# RF2ComLong.net
KiCad netlist of a schematic drawn in EAGLE
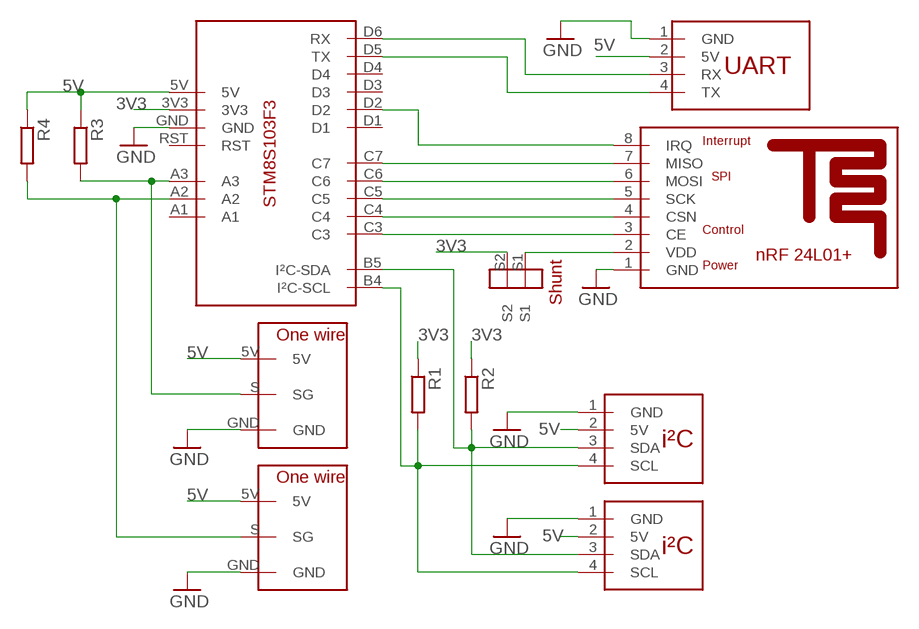
[diagram p0: schematic, sheet 1]

(export (version "E")
  (design (tool "Eeschema 10.0.6"))
  (components
    (comp (ref "R1")
      (value "1k")
      (footprint "eagle-import:R1206")
      (libsource (lib "eagle-import") (part "R-EU_R1206"))
    )
    (comp (ref "R2")
      (value "1k")
      (footprint "eagle-import:R1206")
      (libsource (lib "eagle-import") (part "R-EU_R1206"))
    )
    (comp (ref "R3")
      (value "1k")
      (footprint "eagle-import:R1206")
      (libsource (lib "eagle-import") (part "R-EU_R1206"))
    )
    (comp (ref "R4")
      (value "1k")
      (footprint "eagle-import:R1206")
      (libsource (lib "eagle-import") (part "R-EU_R1206"))
    )
    (comp (ref "U$1")
      (value "STM8S103F3-DEVKITMINI")
      (footprint "eagle-import:STM8S103F3-DEVKIT-MINI")
      (libsource (lib "eagle-import") (part "STM8S103F3-DEVKITMINI"))
    )
    (comp (ref "U$2")
      (value "NRF24L01+REFDESIGNMINI")
      (footprint "eagle-import:NRF24L01+REFDESIGN-MINI")
      (libsource (lib "eagle-import") (part "NRF24L01+REFDESIGNMINI"))
    )
    (comp (ref "U$3")
      (value "UARTMINI")
      (footprint "eagle-import:UART-MINI")
      (libsource (lib "eagle-import") (part "UARTMINI"))
    )
    (comp (ref "U$4")
      (value "I2CMINI")
      (footprint "eagle-import:I2C-MINI")
      (libsource (lib "eagle-import") (part "I2CMINI"))
    )
    (comp (ref "U$5")
      (value "ONE_WIRE")
      (footprint "eagle-import:ONE_WIRE")
      (libsource (lib "eagle-import") (part "ONE_WIRE"))
    )
    (comp (ref "U$6")
      (value "ONE_WIRE")
      (footprint "eagle-import:ONE_WIRE")
      (libsource (lib "eagle-import") (part "ONE_WIRE"))
    )
    (comp (ref "U$7")
      (value "I2CMINI")
      (footprint "eagle-import:I2C-MINI")
      (libsource (lib "eagle-import") (part "I2CMINI"))
    )
    (comp (ref "U$8")
      (value "SMD_SHUNT")
      (footprint "eagle-import:SMD_SHUNT")
      (libsource (lib "eagle-import") (part "SMD_SHUNT"))
    )
  )
  (nets
    (net (code "1") (name "/3V3") (class "Default")
      (node (ref "R1") (pin "1") (pinfunction "1_1") (pintype "passive"))
      (node (ref "R2") (pin "1") (pinfunction "1_1") (pintype "passive"))
      (node (ref "U$1") (pin "3V3") (pinfunction "3V3_3V3") (pintype "bidirectional"))
      (node (ref "U$8") (pin "S2") (pinfunction "S2_S2") (pintype "bidirectional"))
    )
    (net (code "2") (name "/5V") (class "Default")
      (node (ref "R3") (pin "1") (pinfunction "1_1") (pintype "passive"))
      (node (ref "R4") (pin "1") (pinfunction "1_1") (pintype "passive"))
      (node (ref "U$1") (pin "5V") (pinfunction "5V_5V") (pintype "bidirectional"))
      (node (ref "U$3") (pin "2") (pinfunction "5V_2") (pintype "bidirectional"))
      (node (ref "U$4") (pin "2") (pinfunction "5V_2") (pintype "bidirectional"))
      (node (ref "U$5") (pin "5V") (pinfunction "5V_5V") (pintype "bidirectional"))
      (node (ref "U$6") (pin "5V") (pinfunction "5V_5V") (pintype "bidirectional"))
      (node (ref "U$7") (pin "2") (pinfunction "5V_2") (pintype "bidirectional"))
    )
    (net (code "3") (name "GND") (class "Default")
      (node (ref "U$1") (pin "GND") (pinfunction "GND_GND") (pintype "bidirectional"))
      (node (ref "U$2") (pin "1") (pinfunction "GND_1") (pintype "bidirectional"))
      (node (ref "U$3") (pin "1") (pinfunction "GND_1") (pintype "bidirectional"))
      (node (ref "U$4") (pin "1") (pinfunction "GND_1") (pintype "bidirectional"))
      (node (ref "U$5") (pin "GND") (pinfunction "GND_GND") (pintype "bidirectional"))
      (node (ref "U$6") (pin "GND") (pinfunction "GND_GND") (pintype "bidirectional"))
      (node (ref "U$7") (pin "1") (pinfunction "GND_1") (pintype "bidirectional"))
    )
    (net (code "4") (name "Net-(U$1-I²C-SCL)") (class "Default")
      (node (ref "R1") (pin "2") (pinfunction "2_2") (pintype "passive"))
      (node (ref "U$1") (pin "B4") (pinfunction "I²C-SCL_B4") (pintype "bidirectional"))
      (node (ref "U$4") (pin "4") (pinfunction "SCL_4") (pintype "bidirectional"))
      (node (ref "U$7") (pin "4") (pinfunction "SCL_4") (pintype "bidirectional"))
    )
    (net (code "5") (name "Net-(U$1-I²C-SDA)") (class "Default")
      (node (ref "R2") (pin "2") (pinfunction "2_2") (pintype "passive"))
      (node (ref "U$1") (pin "B5") (pinfunction "I²C-SDA_B5") (pintype "bidirectional"))
      (node (ref "U$4") (pin "3") (pinfunction "SDA_3") (pintype "bidirectional"))
      (node (ref "U$7") (pin "3") (pinfunction "SDA_3") (pintype "bidirectional"))
    )
    (net (code "6") (name "Net-(U$1-RX)") (class "Default")
      (node (ref "U$1") (pin "D6") (pinfunction "RX_D6") (pintype "bidirectional"))
      (node (ref "U$3") (pin "3") (pinfunction "RX_3") (pintype "bidirectional"))
    )
    (net (code "7") (name "Net-(U$1-TX)") (class "Default")
      (node (ref "U$1") (pin "D5") (pinfunction "TX_D5") (pintype "bidirectional"))
      (node (ref "U$3") (pin "4") (pinfunction "TX_4") (pintype "bidirectional"))
    )
    (net (code "8") (name "Net-(U$2-CE)") (class "Default")
      (node (ref "U$1") (pin "C3") (pinfunction "C3_C3") (pintype "bidirectional"))
      (node (ref "U$2") (pin "3") (pinfunction "CE_3") (pintype "bidirectional"))
    )
    (net (code "9") (name "Net-(U$2-CSN)") (class "Default")
      (node (ref "U$1") (pin "C4") (pinfunction "C4_C4") (pintype "bidirectional"))
      (node (ref "U$2") (pin "4") (pinfunction "CSN_4") (pintype "bidirectional"))
    )
    (net (code "10") (name "Net-(U$2-IRQ)") (class "Default")
      (node (ref "U$1") (pin "D2") (pinfunction "D2_D2") (pintype "bidirectional"))
      (node (ref "U$2") (pin "8") (pinfunction "IRQ_8") (pintype "bidirectional"))
    )
    (net (code "11") (name "Net-(U$2-MISO)") (class "Default")
      (node (ref "U$1") (pin "C7") (pinfunction "C7_C7") (pintype "bidirectional"))
      (node (ref "U$2") (pin "7") (pinfunction "MISO_7") (pintype "bidirectional"))
    )
    (net (code "12") (name "Net-(U$2-MOSI)") (class "Default")
      (node (ref "U$1") (pin "C6") (pinfunction "C6_C6") (pintype "bidirectional"))
      (node (ref "U$2") (pin "6") (pinfunction "MOSI_6") (pintype "bidirectional"))
    )
    (net (code "13") (name "Net-(U$2-SCK)") (class "Default")
      (node (ref "U$1") (pin "C5") (pinfunction "C5_C5") (pintype "bidirectional"))
      (node (ref "U$2") (pin "5") (pinfunction "SCK_5") (pintype "bidirectional"))
    )
    (net (code "14") (name "Net-(U$2-VDD)") (class "Default")
      (node (ref "U$2") (pin "2") (pinfunction "VDD_2") (pintype "bidirectional"))
      (node (ref "U$8") (pin "S1") (pinfunction "S1_S1") (pintype "bidirectional"))
    )
    (net (code "15") (name "Net-(U$5-SG)") (class "Default")
      (node (ref "R4") (pin "2") (pinfunction "2_2") (pintype "passive"))
      (node (ref "U$1") (pin "A2") (pinfunction "A2_A2") (pintype "bidirectional"))
      (node (ref "U$5") (pin "S") (pinfunction "SG_S") (pintype "bidirectional"))
    )
    (net (code "16") (name "Net-(U$6-SG)") (class "Default")
      (node (ref "R3") (pin "2") (pinfunction "2_2") (pintype "passive"))
      (node (ref "U$1") (pin "A3") (pinfunction "A3_A3") (pintype "bidirectional"))
      (node (ref "U$6") (pin "S") (pinfunction "SG_S") (pintype "bidirectional"))
    )
    (net (code "17") (name "unconnected-(U$1-PadA1)") (class "Default")
      (node (ref "U$1") (pin "A1") (pinfunction "A1_A1") (pintype "bidirectional"))
    )
    (net (code "18") (name "unconnected-(U$1-PadD1)") (class "Default")
      (node (ref "U$1") (pin "D1") (pinfunction "D1_D1") (pintype "bidirectional"))
    )
    (net (code "19") (name "unconnected-(U$1-PadD3)") (class "Default")
      (node (ref "U$1") (pin "D3") (pinfunction "D3_D3") (pintype "bidirectional"))
    )
    (net (code "20") (name "unconnected-(U$1-PadD4)") (class "Default")
      (node (ref "U$1") (pin "D4") (pinfunction "D4_D4") (pintype "bidirectional"))
    )
    (net (code "21") (name "unconnected-(U$1-PadRST)") (class "Default")
      (node (ref "U$1") (pin "RST") (pinfunction "RST_RST") (pintype "bidirectional"))
    )
  )
)
